# LEDBoard.net
KiCad netlist of a schematic drawn in Altium Designer
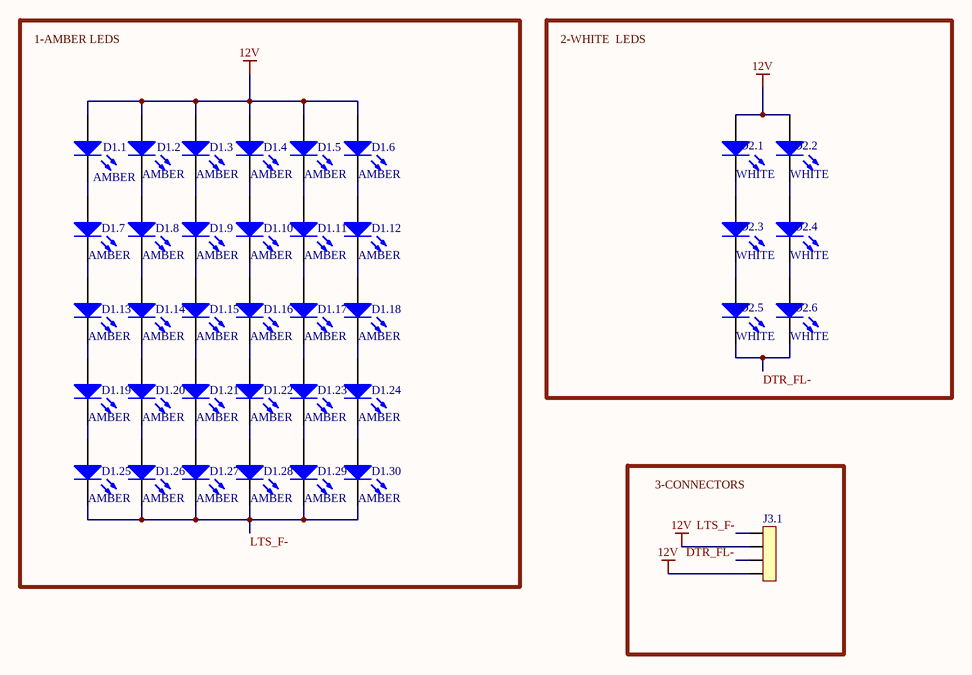
[diagram p0: LEDBoard.SchDoc]

(export (version "E")
  (design (tool "Eeschema 10.0.6"))
  (components
    (comp (ref "D1.1")
      (value "AMBER")
      (footprint "150120AS75000")
      (description "WURTH ELEKTRONIK   150120AS75000   LED, 1206, AMBER, 140MCD, 605NM")
      (libsource (lib "LEDBoard") (part "150120AS75000"))
    )
    (comp (ref "D1.2")
      (value "AMBER")
      (footprint "150120AS75000")
      (description "WURTH ELEKTRONIK   150120AS75000   LED, 1206, AMBER, 140MCD, 605NM")
      (libsource (lib "LEDBoard") (part "150120AS75000"))
    )
    (comp (ref "D1.3")
      (value "AMBER")
      (footprint "150120AS75000")
      (description "WURTH ELEKTRONIK   150120AS75000   LED, 1206, AMBER, 140MCD, 605NM")
      (libsource (lib "LEDBoard") (part "150120AS75000"))
    )
    (comp (ref "D1.4")
      (value "AMBER")
      (footprint "150120AS75000")
      (description "WURTH ELEKTRONIK   150120AS75000   LED, 1206, AMBER, 140MCD, 605NM")
      (libsource (lib "LEDBoard") (part "150120AS75000"))
    )
    (comp (ref "D1.5")
      (value "AMBER")
      (footprint "150120AS75000")
      (description "WURTH ELEKTRONIK   150120AS75000   LED, 1206, AMBER, 140MCD, 605NM")
      (libsource (lib "LEDBoard") (part "150120AS75000"))
    )
    (comp (ref "D1.6")
      (value "AMBER")
      (footprint "150120AS75000")
      (description "WURTH ELEKTRONIK   150120AS75000   LED, 1206, AMBER, 140MCD, 605NM")
      (libsource (lib "LEDBoard") (part "150120AS75000"))
    )
    (comp (ref "D1.7")
      (value "AMBER")
      (footprint "150120AS75000")
      (description "WURTH ELEKTRONIK   150120AS75000   LED, 1206, AMBER, 140MCD, 605NM")
      (libsource (lib "LEDBoard") (part "150120AS75000"))
    )
    (comp (ref "D1.8")
      (value "AMBER")
      (footprint "150120AS75000")
      (description "WURTH ELEKTRONIK   150120AS75000   LED, 1206, AMBER, 140MCD, 605NM")
      (libsource (lib "LEDBoard") (part "150120AS75000"))
    )
    (comp (ref "D1.9")
      (value "AMBER")
      (footprint "150120AS75000")
      (description "WURTH ELEKTRONIK   150120AS75000   LED, 1206, AMBER, 140MCD, 605NM")
      (libsource (lib "LEDBoard") (part "150120AS75000"))
    )
    (comp (ref "D1.10")
      (value "AMBER")
      (footprint "150120AS75000")
      (description "WURTH ELEKTRONIK   150120AS75000   LED, 1206, AMBER, 140MCD, 605NM")
      (libsource (lib "LEDBoard") (part "150120AS75000"))
    )
    (comp (ref "D1.11")
      (value "AMBER")
      (footprint "150120AS75000")
      (description "WURTH ELEKTRONIK   150120AS75000   LED, 1206, AMBER, 140MCD, 605NM")
      (libsource (lib "LEDBoard") (part "150120AS75000"))
    )
    (comp (ref "D1.12")
      (value "AMBER")
      (footprint "150120AS75000")
      (description "WURTH ELEKTRONIK   150120AS75000   LED, 1206, AMBER, 140MCD, 605NM")
      (libsource (lib "LEDBoard") (part "150120AS75000"))
    )
    (comp (ref "D1.13")
      (value "AMBER")
      (footprint "150120AS75000")
      (description "WURTH ELEKTRONIK   150120AS75000   LED, 1206, AMBER, 140MCD, 605NM")
      (libsource (lib "LEDBoard") (part "150120AS75000"))
    )
    (comp (ref "D1.14")
      (value "AMBER")
      (footprint "150120AS75000")
      (description "WURTH ELEKTRONIK   150120AS75000   LED, 1206, AMBER, 140MCD, 605NM")
      (libsource (lib "LEDBoard") (part "150120AS75000"))
    )
    (comp (ref "D1.15")
      (value "AMBER")
      (footprint "150120AS75000")
      (description "WURTH ELEKTRONIK   150120AS75000   LED, 1206, AMBER, 140MCD, 605NM")
      (libsource (lib "LEDBoard") (part "150120AS75000"))
    )
    (comp (ref "D1.16")
      (value "AMBER")
      (footprint "150120AS75000")
      (description "WURTH ELEKTRONIK   150120AS75000   LED, 1206, AMBER, 140MCD, 605NM")
      (libsource (lib "LEDBoard") (part "150120AS75000"))
    )
    (comp (ref "D1.17")
      (value "AMBER")
      (footprint "150120AS75000")
      (description "WURTH ELEKTRONIK   150120AS75000   LED, 1206, AMBER, 140MCD, 605NM")
      (libsource (lib "LEDBoard") (part "150120AS75000"))
    )
    (comp (ref "D1.18")
      (value "AMBER")
      (footprint "150120AS75000")
      (description "WURTH ELEKTRONIK   150120AS75000   LED, 1206, AMBER, 140MCD, 605NM")
      (libsource (lib "LEDBoard") (part "150120AS75000"))
    )
    (comp (ref "D1.19")
      (value "AMBER")
      (footprint "150120AS75000")
      (description "WURTH ELEKTRONIK   150120AS75000   LED, 1206, AMBER, 140MCD, 605NM")
      (libsource (lib "LEDBoard") (part "150120AS75000"))
    )
    (comp (ref "D1.20")
      (value "AMBER")
      (footprint "150120AS75000")
      (description "WURTH ELEKTRONIK   150120AS75000   LED, 1206, AMBER, 140MCD, 605NM")
      (libsource (lib "LEDBoard") (part "150120AS75000"))
    )
    (comp (ref "D1.21")
      (value "AMBER")
      (footprint "150120AS75000")
      (description "WURTH ELEKTRONIK   150120AS75000   LED, 1206, AMBER, 140MCD, 605NM")
      (libsource (lib "LEDBoard") (part "150120AS75000"))
    )
    (comp (ref "D1.22")
      (value "AMBER")
      (footprint "150120AS75000")
      (description "WURTH ELEKTRONIK   150120AS75000   LED, 1206, AMBER, 140MCD, 605NM")
      (libsource (lib "LEDBoard") (part "150120AS75000"))
    )
    (comp (ref "D1.23")
      (value "AMBER")
      (footprint "150120AS75000")
      (description "WURTH ELEKTRONIK   150120AS75000   LED, 1206, AMBER, 140MCD, 605NM")
      (libsource (lib "LEDBoard") (part "150120AS75000"))
    )
    (comp (ref "D1.24")
      (value "AMBER")
      (footprint "150120AS75000")
      (description "WURTH ELEKTRONIK   150120AS75000   LED, 1206, AMBER, 140MCD, 605NM")
      (libsource (lib "LEDBoard") (part "150120AS75000"))
    )
    (comp (ref "D1.25")
      (value "AMBER")
      (footprint "150120AS75000")
      (description "WURTH ELEKTRONIK   150120AS75000   LED, 1206, AMBER, 140MCD, 605NM")
      (libsource (lib "LEDBoard") (part "150120AS75000"))
    )
    (comp (ref "D1.26")
      (value "AMBER")
      (footprint "150120AS75000")
      (description "WURTH ELEKTRONIK   150120AS75000   LED, 1206, AMBER, 140MCD, 605NM")
      (libsource (lib "LEDBoard") (part "150120AS75000"))
    )
    (comp (ref "D1.27")
      (value "AMBER")
      (footprint "150120AS75000")
      (description "WURTH ELEKTRONIK   150120AS75000   LED, 1206, AMBER, 140MCD, 605NM")
      (libsource (lib "LEDBoard") (part "150120AS75000"))
    )
    (comp (ref "D1.28")
      (value "AMBER")
      (footprint "150120AS75000")
      (description "WURTH ELEKTRONIK   150120AS75000   LED, 1206, AMBER, 140MCD, 605NM")
      (libsource (lib "LEDBoard") (part "150120AS75000"))
    )
    (comp (ref "D1.29")
      (value "AMBER")
      (footprint "150120AS75000")
      (description "WURTH ELEKTRONIK   150120AS75000   LED, 1206, AMBER, 140MCD, 605NM")
      (libsource (lib "LEDBoard") (part "150120AS75000"))
    )
    (comp (ref "D1.30")
      (value "AMBER")
      (footprint "150120AS75000")
      (description "WURTH ELEKTRONIK   150120AS75000   LED, 1206, AMBER, 140MCD, 605NM")
      (libsource (lib "LEDBoard") (part "150120AS75000"))
    )
    (comp (ref "D2.1")
      (value "WHITE")
      (footprint "HSMW-C170-U0000")
      (description "Led, White, 670MCD, 0805")
      (libsource (lib "LEDBoard") (part "HSMW-C170-U0000"))
    )
    (comp (ref "D2.2")
      (value "WHITE")
      (footprint "HSMW-C170-U0000")
      (description "Led, White, 670MCD, 0805")
      (libsource (lib "LEDBoard") (part "HSMW-C170-U0000"))
    )
    (comp (ref "D2.3")
      (value "WHITE")
      (footprint "HSMW-C170-U0000")
      (description "Led, White, 670MCD, 0805")
      (libsource (lib "LEDBoard") (part "HSMW-C170-U0000"))
    )
    (comp (ref "D2.4")
      (value "WHITE")
      (footprint "HSMW-C170-U0000")
      (description "Led, White, 670MCD, 0805")
      (libsource (lib "LEDBoard") (part "HSMW-C170-U0000"))
    )
    (comp (ref "D2.5")
      (value "WHITE")
      (footprint "HSMW-C170-U0000")
      (description "Led, White, 670MCD, 0805")
      (libsource (lib "LEDBoard") (part "HSMW-C170-U0000"))
    )
    (comp (ref "D2.6")
      (value "WHITE")
      (footprint "HSMW-C170-U0000")
      (description "Led, White, 670MCD, 0805")
      (libsource (lib "LEDBoard") (part "HSMW-C170-U0000"))
    )
    (comp (ref "J3.1")
      (value "B04B-XASK-1-A(LF)(SN)")
      (footprint "B04B-XASK-1-A")
      (description "XA Series 4 Position 2.5mm Pitch Top Entry with Boss ThroughHole Shrouded Header")
      (libsource (lib "LEDBoard") (part "B04B-XASK-1-A(LF)(SN)"))
    )
  )
  (nets
    (net (code "1") (name "/DTR_FL-") (class "Default")
      (node (ref "D2.5") (pin "1") (pinfunction "K_1") (pintype "passive"))
      (node (ref "D2.6") (pin "1") (pinfunction "K_1") (pintype "passive"))
      (node (ref "J3.1") (pin "3") (pinfunction "3_3") (pintype "passive"))
    )
    (net (code "2") (name "/LTS_F-") (class "Default")
      (node (ref "D1.25") (pin "1") (pinfunction "K_1") (pintype "passive"))
      (node (ref "D1.26") (pin "1") (pinfunction "K_1") (pintype "passive"))
      (node (ref "D1.27") (pin "1") (pinfunction "K_1") (pintype "passive"))
      (node (ref "D1.28") (pin "1") (pinfunction "K_1") (pintype "passive"))
      (node (ref "D1.29") (pin "1") (pinfunction "K_1") (pintype "passive"))
      (node (ref "D1.30") (pin "1") (pinfunction "K_1") (pintype "passive"))
      (node (ref "J3.1") (pin "1") (pinfunction "1_1") (pintype "passive"))
    )
    (net (code "3") (name "12V") (class "Default")
      (node (ref "D1.1") (pin "2") (pinfunction "A_2") (pintype "passive"))
      (node (ref "D1.2") (pin "2") (pinfunction "A_2") (pintype "passive"))
      (node (ref "D1.3") (pin "2") (pinfunction "A_2") (pintype "passive"))
      (node (ref "D1.4") (pin "2") (pinfunction "A_2") (pintype "passive"))
      (node (ref "D1.5") (pin "2") (pinfunction "A_2") (pintype "passive"))
      (node (ref "D1.6") (pin "2") (pinfunction "A_2") (pintype "passive"))
      (node (ref "D2.1") (pin "2") (pinfunction "A_2") (pintype "passive"))
      (node (ref "D2.2") (pin "2") (pinfunction "A_2") (pintype "passive"))
      (node (ref "J3.1") (pin "2") (pinfunction "2_2") (pintype "passive"))
      (node (ref "J3.1") (pin "4") (pinfunction "4_4") (pintype "passive"))
    )
    (net (code "4") (name "Net-(D1.1-K)") (class "Default")
      (node (ref "D1.1") (pin "1") (pinfunction "K_1") (pintype "passive"))
      (node (ref "D1.7") (pin "2") (pinfunction "A_2") (pintype "passive"))
    )
    (net (code "5") (name "Net-(D1.2-K)") (class "Default")
      (node (ref "D1.2") (pin "1") (pinfunction "K_1") (pintype "passive"))
      (node (ref "D1.8") (pin "2") (pinfunction "A_2") (pintype "passive"))
    )
    (net (code "6") (name "Net-(D1.3-K)") (class "Default")
      (node (ref "D1.3") (pin "1") (pinfunction "K_1") (pintype "passive"))
      (node (ref "D1.9") (pin "2") (pinfunction "A_2") (pintype "passive"))
    )
    (net (code "7") (name "Net-(D1.10-A)") (class "Default")
      (node (ref "D1.10") (pin "2") (pinfunction "A_2") (pintype "passive"))
      (node (ref "D1.4") (pin "1") (pinfunction "K_1") (pintype "passive"))
    )
    (net (code "8") (name "Net-(D1.10-K)") (class "Default")
      (node (ref "D1.10") (pin "1") (pinfunction "K_1") (pintype "passive"))
      (node (ref "D1.16") (pin "2") (pinfunction "A_2") (pintype "passive"))
    )
    (net (code "9") (name "Net-(D1.11-A)") (class "Default")
      (node (ref "D1.11") (pin "2") (pinfunction "A_2") (pintype "passive"))
      (node (ref "D1.5") (pin "1") (pinfunction "K_1") (pintype "passive"))
    )
    (net (code "10") (name "Net-(D1.11-K)") (class "Default")
      (node (ref "D1.11") (pin "1") (pinfunction "K_1") (pintype "passive"))
      (node (ref "D1.17") (pin "2") (pinfunction "A_2") (pintype "passive"))
    )
    (net (code "11") (name "Net-(D1.12-A)") (class "Default")
      (node (ref "D1.12") (pin "2") (pinfunction "A_2") (pintype "passive"))
      (node (ref "D1.6") (pin "1") (pinfunction "K_1") (pintype "passive"))
    )
    (net (code "12") (name "Net-(D1.12-K)") (class "Default")
      (node (ref "D1.12") (pin "1") (pinfunction "K_1") (pintype "passive"))
      (node (ref "D1.18") (pin "2") (pinfunction "A_2") (pintype "passive"))
    )
    (net (code "13") (name "Net-(D1.13-A)") (class "Default")
      (node (ref "D1.13") (pin "2") (pinfunction "A_2") (pintype "passive"))
      (node (ref "D1.7") (pin "1") (pinfunction "K_1") (pintype "passive"))
    )
    (net (code "14") (name "Net-(D1.13-K)") (class "Default")
      (node (ref "D1.13") (pin "1") (pinfunction "K_1") (pintype "passive"))
      (node (ref "D1.19") (pin "2") (pinfunction "A_2") (pintype "passive"))
    )
    (net (code "15") (name "Net-(D1.14-A)") (class "Default")
      (node (ref "D1.14") (pin "2") (pinfunction "A_2") (pintype "passive"))
      (node (ref "D1.8") (pin "1") (pinfunction "K_1") (pintype "passive"))
    )
    (net (code "16") (name "Net-(D1.14-K)") (class "Default")
      (node (ref "D1.14") (pin "1") (pinfunction "K_1") (pintype "passive"))
      (node (ref "D1.20") (pin "2") (pinfunction "A_2") (pintype "passive"))
    )
    (net (code "17") (name "Net-(D1.15-A)") (class "Default")
      (node (ref "D1.15") (pin "2") (pinfunction "A_2") (pintype "passive"))
      (node (ref "D1.9") (pin "1") (pinfunction "K_1") (pintype "passive"))
    )
    (net (code "18") (name "Net-(D1.15-K)") (class "Default")
      (node (ref "D1.15") (pin "1") (pinfunction "K_1") (pintype "passive"))
      (node (ref "D1.21") (pin "2") (pinfunction "A_2") (pintype "passive"))
    )
    (net (code "19") (name "Net-(D1.16-K)") (class "Default")
      (node (ref "D1.16") (pin "1") (pinfunction "K_1") (pintype "passive"))
      (node (ref "D1.22") (pin "2") (pinfunction "A_2") (pintype "passive"))
    )
    (net (code "20") (name "Net-(D1.17-K)") (class "Default")
      (node (ref "D1.17") (pin "1") (pinfunction "K_1") (pintype "passive"))
      (node (ref "D1.23") (pin "2") (pinfunction "A_2") (pintype "passive"))
    )
    (net (code "21") (name "Net-(D1.18-K)") (class "Default")
      (node (ref "D1.18") (pin "1") (pinfunction "K_1") (pintype "passive"))
      (node (ref "D1.24") (pin "2") (pinfunction "A_2") (pintype "passive"))
    )
    (net (code "22") (name "Net-(D1.19-K)") (class "Default")
      (node (ref "D1.19") (pin "1") (pinfunction "K_1") (pintype "passive"))
      (node (ref "D1.25") (pin "2") (pinfunction "A_2") (pintype "passive"))
    )
    (net (code "23") (name "Net-(D1.20-K)") (class "Default")
      (node (ref "D1.20") (pin "1") (pinfunction "K_1") (pintype "passive"))
      (node (ref "D1.26") (pin "2") (pinfunction "A_2") (pintype "passive"))
    )
    (net (code "24") (name "Net-(D1.21-K)") (class "Default")
      (node (ref "D1.21") (pin "1") (pinfunction "K_1") (pintype "passive"))
      (node (ref "D1.27") (pin "2") (pinfunction "A_2") (pintype "passive"))
    )
    (net (code "25") (name "Net-(D1.22-K)") (class "Default")
      (node (ref "D1.22") (pin "1") (pinfunction "K_1") (pintype "passive"))
      (node (ref "D1.28") (pin "2") (pinfunction "A_2") (pintype "passive"))
    )
    (net (code "26") (name "Net-(D1.23-K)") (class "Default")
      (node (ref "D1.23") (pin "1") (pinfunction "K_1") (pintype "passive"))
      (node (ref "D1.29") (pin "2") (pinfunction "A_2") (pintype "passive"))
    )
    (net (code "27") (name "Net-(D1.24-K)") (class "Default")
      (node (ref "D1.24") (pin "1") (pinfunction "K_1") (pintype "passive"))
      (node (ref "D1.30") (pin "2") (pinfunction "A_2") (pintype "passive"))
    )
    (net (code "28") (name "Net-(D2.1-K)") (class "Default")
      (node (ref "D2.1") (pin "1") (pinfunction "K_1") (pintype "passive"))
      (node (ref "D2.3") (pin "2") (pinfunction "A_2") (pintype "passive"))
    )
    (net (code "29") (name "Net-(D2.2-K)") (class "Default")
      (node (ref "D2.2") (pin "1") (pinfunction "K_1") (pintype "passive"))
      (node (ref "D2.4") (pin "2") (pinfunction "A_2") (pintype "passive"))
    )
    (net (code "30") (name "Net-(D2.3-K)") (class "Default")
      (node (ref "D2.3") (pin "1") (pinfunction "K_1") (pintype "passive"))
      (node (ref "D2.5") (pin "2") (pinfunction "A_2") (pintype "passive"))
    )
    (net (code "31") (name "Net-(D2.4-K)") (class "Default")
      (node (ref "D2.4") (pin "1") (pinfunction "K_1") (pintype "passive"))
      (node (ref "D2.6") (pin "2") (pinfunction "A_2") (pintype "passive"))
    )
  )
)
